# Sheet2.net
KiCad netlist of a schematic drawn in Altium Designer
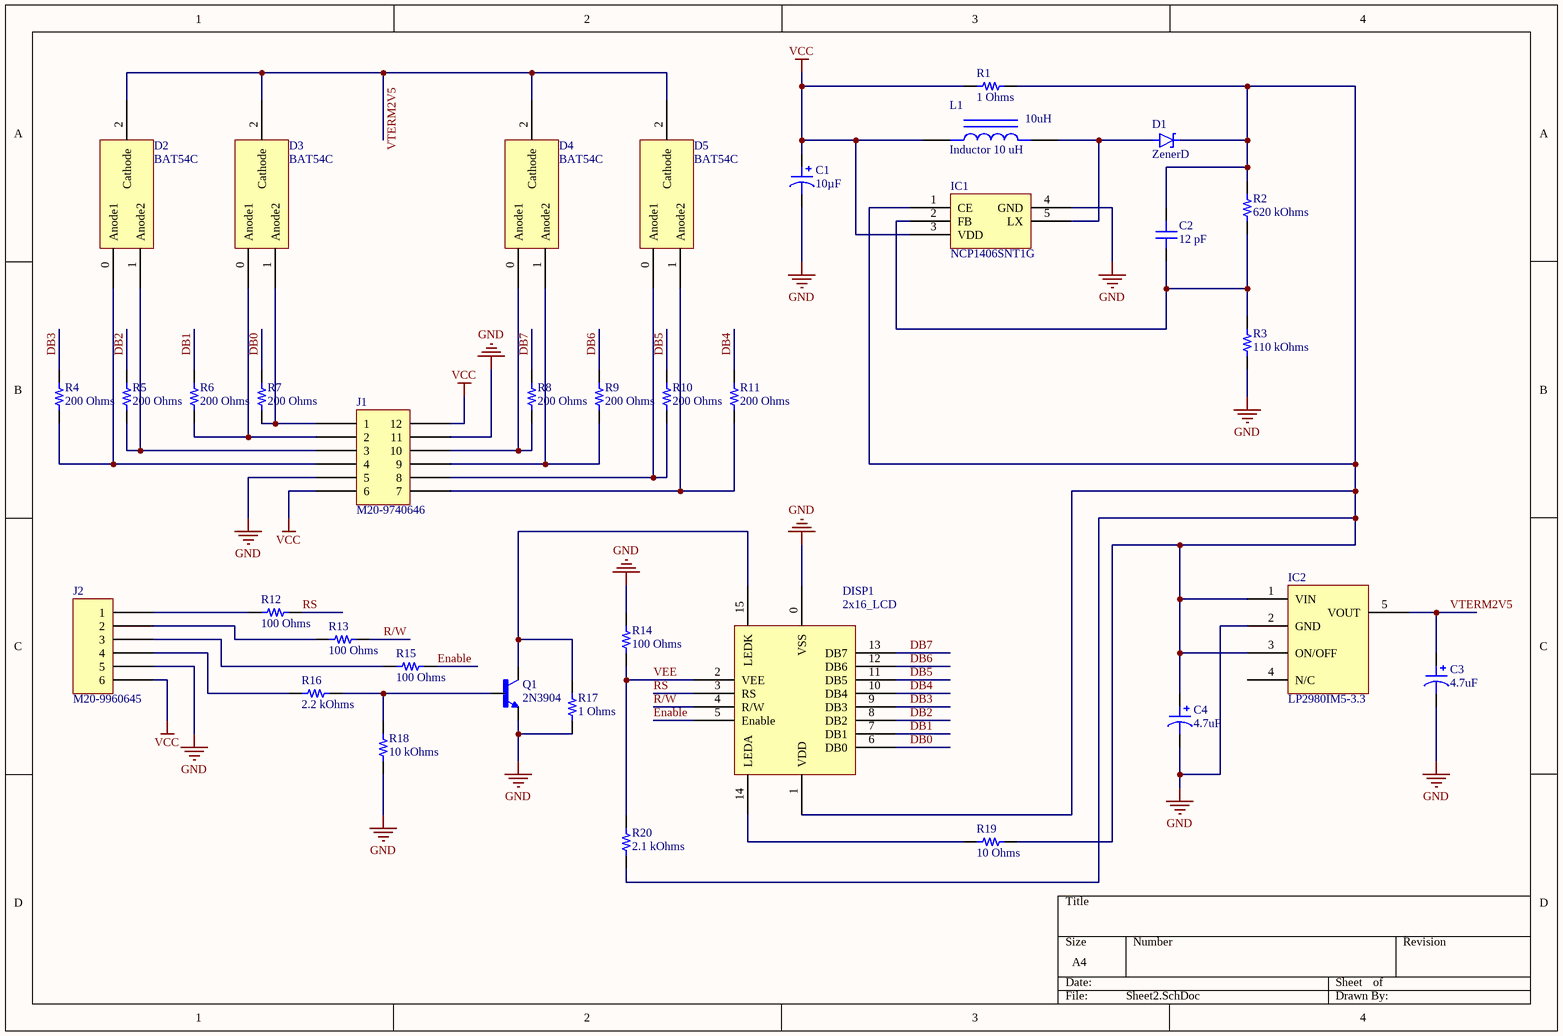
[diagram p0: Sheet2.SchDoc]

(export (version "E")
  (design (tool "Eeschema 10.0.6"))
  (components
    (comp (ref "C1")
      (value "10µF")
      (footprint "CAP TH ALUM ELEC D5.00mm S2.00mm H11.00mm")
      (description "CAP ALUM 10UF 20% 16V RADIAL")
      (fields
        (field (name "PART NUMBER") "ECE-A1CN100U")
        (field (name "MANUFACTURER") "Panasonic Electronic Components")
      )
      (libsource (lib "Celestial Altium Library - altium_library") (part "Polarised Capacitor"))
    )
    (comp (ref "C2")
      (value "12 pF")
      (footprint "CAP 0805_2012")
      (description "CAP CER 12PF 16V C0G/NP0 0805")
      (fields
        (field (name "PART NUMBER") "VJ0805A120FXJCW1BC")
        (field (name "MANUFACTURER") "Vishay Vitramon")
      )
      (libsource (lib "Celestial Altium Library - altium_library") (part "Capacitor"))
    )
    (comp (ref "C3")
      (value "4.7uF")
      (footprint "CAP TH ALUM ELEC D5.00mm S2.00mm H11.00mm")
      (description "CAP ALUM 4.7UF 20% 16V RADIAL")
      (fields
        (field (name "PART NUMBER") "ECE-A1CN100U")
        (field (name "MANUFACTURER") "Panasonic Electronic Components")
      )
      (libsource (lib "Celestial Altium Library - altium_library") (part "Polarised Capacitor"))
    )
    (comp (ref "C4")
      (value "4.7uF")
      (footprint "CAP TH ALUM ELEC D5.00mm S2.00mm H11.00mm")
      (description "CAP ALUM 4.7UF 20% 16V RADIAL")
      (fields
        (field (name "PART NUMBER") "ECE-A1CN100U")
        (field (name "MANUFACTURER") "Panasonic Electronic Components")
      )
      (libsource (lib "Celestial Altium Library - altium_library") (part "Polarised Capacitor"))
    )
    (comp (ref "D1") (value "ZenerD") (footprint "ZenerD") (libsource (lib "Schlib1") (part "ZenerD")))
    (comp (ref "D2") (value "BAT54C") (footprint "BAT54C") (libsource (lib "Schlib1") (part "BAT54C")))
    (comp (ref "D3") (value "BAT54C") (footprint "BAT54C") (libsource (lib "Schlib1") (part "BAT54C")))
    (comp (ref "D4") (value "BAT54C") (footprint "BAT54C") (libsource (lib "Schlib1") (part "BAT54C")))
    (comp (ref "D5") (value "BAT54C") (footprint "BAT54C") (libsource (lib "Schlib1") (part "BAT54C")))
    (comp (ref "DISP1")
      (value "2x16_LCD")
      (footprint "2x16_LCD")
      (libsource (lib "Schlib1") (part "2x16_LCD"))
    )
    (comp (ref "IC1")
      (value "NCP1406SNT1G")
      (footprint "NCP1406SNT1G")
      (libsource (lib "Schlib1") (part "NCP1406SNT1G"))
    )
    (comp (ref "IC2")
      (value "LP2980IM5-3.3")
      (footprint "LP2980IM5-3.3")
      (libsource (lib "Schlib1") (part "LP2980IM5-3.3"))
    )
    (comp (ref "J1")
      (value "M20-9740646")
      (footprint "HARWIN M20-9740645")
      (description "CONN HEADER R/A 12POS 2.54MM")
      (fields (field (name "MANUFACTURER") "Harwin Inc."))
      (libsource (lib "Celestial Altium Library - altium_library") (part "2X6 PIN DU"))
    )
    (comp (ref "J2")
      (value "M20-9960645")
      (footprint "HARWIN M20-9960645")
      (description "CONN HEADER R/A 6POS 2.54MM")
      (fields (field (name "MANUFACTURER") "Harwin Inc."))
      (libsource (lib "Celestial Altium Library - altium_library") (part "6 Pin"))
    )
    (comp (ref "L1")
      (value "Inductor 10 uH")
      (footprint "Inductor")
      (libsource (lib "Schlib1") (part "Inductor 2.2 uH"))
    )
    (comp (ref "Q1") (value "2N3904") (footprint "2N3904") (libsource (lib "Schlib1") (part "2N3904")))
    (comp (ref "R1")
      (value "1 Ohms")
      (footprint "RES 0805_2012")
      (description "RES 1 OHM 5% 1/4W 0805")
      (fields
        (field (name "PART NUMBER") "SG73S2ATTD1R0J")
        (field (name "MANUFACTURER") "KOA Speer Electronics, Inc.")
      )
      (libsource (lib "Celestial Altium Library - altium_library") (part "Resistor"))
    )
    (comp (ref "R2")
      (value "620 kOhms")
      (footprint "RES 0805_2012")
      (description "RES SMD 620K OHM 0.1% 1/4W 0805")
      (fields
        (field (name "PART NUMBER") "ERJ-PB6B6203V")
        (field (name "MANUFACTURER") "Panasonic Electronic Components")
      )
      (libsource (lib "Celestial Altium Library - altium_library") (part "Resistor"))
    )
    (comp (ref "R3")
      (value "110 kOhms")
      (footprint "RES 0805_2012")
      (description "RES 110K OHM 5% 1/4W 0805")
      (fields
        (field (name "PART NUMBER") "RK73B2ATTD114J")
        (field (name "MANUFACTURER") "KOA Speer Electronics, Inc.")
      )
      (libsource (lib "Celestial Altium Library - altium_library") (part "Resistor"))
    )
    (comp (ref "R4")
      (value "200 Ohms")
      (footprint "RES 0805_2012")
      (description "RES 200 OHM 5% 1/4W 0805")
      (fields
        (field (name "PART NUMBER") "RK73B2ATTD201J")
        (field (name "MANUFACTURER") "KOA Speer Electronics, Inc.")
      )
      (libsource (lib "Celestial Altium Library - altium_library") (part "Resistor"))
    )
    (comp (ref "R5")
      (value "200 Ohms")
      (footprint "RES 0805_2012")
      (description "RES 200 OHM 5% 1/4W 0805")
      (fields
        (field (name "PART NUMBER") "RK73B2ATTD201J")
        (field (name "MANUFACTURER") "KOA Speer Electronics, Inc.")
      )
      (libsource (lib "Celestial Altium Library - altium_library") (part "Resistor"))
    )
    (comp (ref "R6")
      (value "200 Ohms")
      (footprint "RES 0805_2012")
      (description "RES 200 OHM 5% 1/4W 0805")
      (fields
        (field (name "PART NUMBER") "RK73B2ATTD201J")
        (field (name "MANUFACTURER") "KOA Speer Electronics, Inc.")
      )
      (libsource (lib "Celestial Altium Library - altium_library") (part "Resistor"))
    )
    (comp (ref "R7")
      (value "200 Ohms")
      (footprint "RES 0805_2012")
      (description "RES 200 OHM 5% 1/4W 0805")
      (fields
        (field (name "PART NUMBER") "RK73B2ATTD201J")
        (field (name "MANUFACTURER") "KOA Speer Electronics, Inc.")
      )
      (libsource (lib "Celestial Altium Library - altium_library") (part "Resistor"))
    )
    (comp (ref "R8")
      (value "200 Ohms")
      (footprint "RES 0805_2012")
      (description "RES 200 OHM 5% 1/4W 0805")
      (fields
        (field (name "PART NUMBER") "RK73B2ATTD201J")
        (field (name "MANUFACTURER") "KOA Speer Electronics, Inc.")
      )
      (libsource (lib "Celestial Altium Library - altium_library") (part "Resistor"))
    )
    (comp (ref "R9")
      (value "200 Ohms")
      (footprint "RES 0805_2012")
      (description "RES 200 OHM 5% 1/4W 0805")
      (fields
        (field (name "PART NUMBER") "RK73B2ATTD201J")
        (field (name "MANUFACTURER") "KOA Speer Electronics, Inc.")
      )
      (libsource (lib "Celestial Altium Library - altium_library") (part "Resistor"))
    )
    (comp (ref "R10")
      (value "200 Ohms")
      (footprint "RES 0805_2012")
      (description "RES 200 OHM 5% 1/4W 0805")
      (fields
        (field (name "PART NUMBER") "RK73B2ATTD201J")
        (field (name "MANUFACTURER") "KOA Speer Electronics, Inc.")
      )
      (libsource (lib "Celestial Altium Library - altium_library") (part "Resistor"))
    )
    (comp (ref "R11")
      (value "200 Ohms")
      (footprint "RES 0805_2012")
      (description "RES 200 OHM 5% 1/4W 0805")
      (fields
        (field (name "PART NUMBER") "RK73B2ATTD201J")
        (field (name "MANUFACTURER") "KOA Speer Electronics, Inc.")
      )
      (libsource (lib "Celestial Altium Library - altium_library") (part "Resistor"))
    )
    (comp (ref "R12")
      (value "100 Ohms")
      (footprint "RES 0805_2012")
      (description "RES 100 OHM 5% 1/4W 0805")
      (fields
        (field (name "PART NUMBER") "RK73B2ATTD101J")
        (field (name "MANUFACTURER") "KOA Speer Electronics, Inc.")
      )
      (libsource (lib "Celestial Altium Library - altium_library") (part "Resistor"))
    )
    (comp (ref "R13")
      (value "100 Ohms")
      (footprint "RES 0805_2012")
      (description "RES 100 OHM 5% 1/4W 0805")
      (fields
        (field (name "PART NUMBER") "RK73B2ATTD101J")
        (field (name "MANUFACTURER") "KOA Speer Electronics, Inc.")
      )
      (libsource (lib "Celestial Altium Library - altium_library") (part "Resistor"))
    )
    (comp (ref "R14")
      (value "100 Ohms")
      (footprint "RES 0805_2012")
      (description "RES 100 OHM 5% 1/4W 0805")
      (fields
        (field (name "PART NUMBER") "RK73B2ATTD101J")
        (field (name "MANUFACTURER") "KOA Speer Electronics, Inc.")
      )
      (libsource (lib "Celestial Altium Library - altium_library") (part "Resistor"))
    )
    (comp (ref "R15")
      (value "100 Ohms")
      (footprint "RES 0805_2012")
      (description "RES 100 OHM 5% 1/4W 0805")
      (fields
        (field (name "PART NUMBER") "RK73B2ATTD101J")
        (field (name "MANUFACTURER") "KOA Speer Electronics, Inc.")
      )
      (libsource (lib "Celestial Altium Library - altium_library") (part "Resistor"))
    )
    (comp (ref "R16")
      (value "2.2 kOhms")
      (footprint "RES 0805_2012")
      (description "RES 2.2K OHM 5% 1/4W 0805")
      (fields
        (field (name "PART NUMBER") "RK73B2ATTD222J")
        (field (name "MANUFACTURER") "KOA Speer Electronics, Inc.")
      )
      (libsource (lib "Celestial Altium Library - altium_library") (part "Resistor"))
    )
    (comp (ref "R17")
      (value "1 Ohms")
      (footprint "RES 0805_2012")
      (description "RES 1 OHM 5% 1/4W 0805")
      (fields
        (field (name "PART NUMBER") "SG73S2ATTD1R0J")
        (field (name "MANUFACTURER") "KOA Speer Electronics, Inc.")
      )
      (libsource (lib "Celestial Altium Library - altium_library") (part "Resistor"))
    )
    (comp (ref "R18")
      (value "10 kOhms")
      (footprint "RES 0805_2012")
      (description "RES 10K OHM 1% 1/4W 0805")
      (fields
        (field (name "PART NUMBER") "SG73S2ATTD1002F")
        (field (name "MANUFACTURER") "KOA Speer Electronics, Inc.")
      )
      (libsource (lib "Celestial Altium Library - altium_library") (part "Resistor"))
    )
    (comp (ref "R19")
      (value "10 Ohms")
      (footprint "RES 0805_2012")
      (description "RES 10 OHM 1% 1/4W 0805")
      (fields
        (field (name "PART NUMBER") "RNCP0805FTD10R0")
        (field (name "MANUFACTURER") "Stackpole Electronics Inc")
      )
      (libsource (lib "Celestial Altium Library - altium_library") (part "Resistor"))
    )
    (comp (ref "R20")
      (value "2.1 kOhms")
      (footprint "RES 0805_2012")
      (description "RES 2.1K OHM 1% 1/4W 0805")
      (fields
        (field (name "PART NUMBER") "RK73H2ATTD2101F")
        (field (name "MANUFACTURER") "KOA Speer Electronics, Inc.")
      )
      (libsource (lib "Celestial Altium Library - altium_library") (part "Resistor"))
    )
  )
  (nets
    (net (code "2") (name "/DB0") (class "Default")
      (node (ref "DISP1") (pin "6") (pinfunction "DB0_6") (pintype "passive"))
      (node (ref "R7") (pin "1") (pinfunction "1_1") (pintype "passive"))
    )
    (net (code "3") (name "/DB1") (class "Default")
      (node (ref "DISP1") (pin "7") (pinfunction "DB1_7") (pintype "passive"))
      (node (ref "R6") (pin "2") (pinfunction "2_2") (pintype "passive"))
    )
    (net (code "4") (name "/DB2") (class "Default")
      (node (ref "DISP1") (pin "8") (pinfunction "DB2_8") (pintype "passive"))
      (node (ref "R5") (pin "1") (pinfunction "1_1") (pintype "passive"))
    )
    (net (code "5") (name "/DB3") (class "Default")
      (node (ref "DISP1") (pin "9") (pinfunction "DB3_9") (pintype "passive"))
      (node (ref "R4") (pin "1") (pinfunction "1_1") (pintype "passive"))
    )
    (net (code "6") (name "/DB4") (class "Default")
      (node (ref "DISP1") (pin "10") (pinfunction "DB4_10") (pintype "passive"))
      (node (ref "R11") (pin "1") (pinfunction "1_1") (pintype "passive"))
    )
    (net (code "7") (name "/DB5") (class "Default")
      (node (ref "DISP1") (pin "11") (pinfunction "DB5_11") (pintype "passive"))
      (node (ref "R10") (pin "1") (pinfunction "1_1") (pintype "passive"))
    )
    (net (code "8") (name "/DB6") (class "Default")
      (node (ref "DISP1") (pin "12") (pinfunction "DB6_12") (pintype "passive"))
      (node (ref "R9") (pin "1") (pinfunction "1_1") (pintype "passive"))
    )
    (net (code "9") (name "/DB7") (class "Default")
      (node (ref "DISP1") (pin "13") (pinfunction "DB7_13") (pintype "passive"))
      (node (ref "R8") (pin "1") (pinfunction "1_1") (pintype "passive"))
    )
    (net (code "10") (name "/Enable") (class "Default")
      (node (ref "DISP1") (pin "5") (pinfunction "Enable_5") (pintype "passive"))
      (node (ref "R15") (pin "2") (pinfunction "2_2") (pintype "passive"))
    )
    (net (code "11") (name "/RS") (class "Default")
      (node (ref "DISP1") (pin "3") (pinfunction "RS_3") (pintype "passive"))
      (node (ref "R12") (pin "2") (pinfunction "2_2") (pintype "passive"))
    )
    (net (code "12") (name "/R{slash}W") (class "Default")
      (node (ref "DISP1") (pin "4") (pinfunction "R/W_4") (pintype "passive"))
      (node (ref "R13") (pin "2") (pinfunction "2_2") (pintype "passive"))
    )
    (net (code "13") (name "/VEE") (class "Default")
      (node (ref "DISP1") (pin "2") (pinfunction "VEE_2") (pintype "passive"))
      (node (ref "R14") (pin "2") (pinfunction "2_2") (pintype "passive"))
      (node (ref "R20") (pin "2") (pinfunction "2_2") (pintype "passive"))
    )
    (net (code "14") (name "/VTERM2V5") (class "Default")
      (node (ref "C3") (pin "1") (pinfunction "1_1") (pintype "passive"))
      (node (ref "D2") (pin "2") (pinfunction "Cathode_2") (pintype "passive"))
      (node (ref "D3") (pin "2") (pinfunction "Cathode_2") (pintype "passive"))
      (node (ref "D4") (pin "2") (pinfunction "Cathode_2") (pintype "passive"))
      (node (ref "D5") (pin "2") (pinfunction "Cathode_2") (pintype "passive"))
      (node (ref "IC2") (pin "5") (pinfunction "VOUT_5") (pintype "passive"))
    )
    (net (code "15") (name "GND") (class "Default")
      (node (ref "C1") (pin "2") (pinfunction "2_2") (pintype "passive"))
      (node (ref "C3") (pin "2") (pinfunction "2_2") (pintype "passive"))
      (node (ref "C4") (pin "2") (pinfunction "2_2") (pintype "passive"))
      (node (ref "DISP1") (pin "0") (pinfunction "VSS_0") (pintype "passive"))
      (node (ref "IC1") (pin "4") (pinfunction "GND_4") (pintype "passive"))
      (node (ref "IC2") (pin "2") (pinfunction "GND_2") (pintype "passive"))
      (node (ref "J1") (pin "11") (pinfunction "11_11") (pintype "passive"))
      (node (ref "J1") (pin "5") (pinfunction "5_5") (pintype "passive"))
      (node (ref "J2") (pin "5") (pinfunction "5_5") (pintype "passive"))
      (node (ref "Q1") (pin "1") (pinfunction "E_1") (pintype "passive"))
      (node (ref "R14") (pin "1") (pinfunction "1_1") (pintype "passive"))
      (node (ref "R17") (pin "1") (pinfunction "1_1") (pintype "passive"))
      (node (ref "R18") (pin "1") (pinfunction "1_1") (pintype "passive"))
      (node (ref "R3") (pin "1") (pinfunction "1_1") (pintype "passive"))
    )
    (net (code "16") (name "Net-(D2-Anode1)") (class "Default")
      (node (ref "D2") (pin "0") (pinfunction "Anode1_0") (pintype "passive"))
      (node (ref "J1") (pin "4") (pinfunction "4_4") (pintype "passive"))
      (node (ref "R4") (pin "2") (pinfunction "2_2") (pintype "passive"))
    )
    (net (code "17") (name "Net-(D2-Anode2)") (class "Default")
      (node (ref "D2") (pin "1") (pinfunction "Anode2_1") (pintype "passive"))
      (node (ref "J1") (pin "3") (pinfunction "3_3") (pintype "passive"))
      (node (ref "R5") (pin "2") (pinfunction "2_2") (pintype "passive"))
    )
    (net (code "18") (name "Net-(D3-Anode1)") (class "Default")
      (node (ref "D3") (pin "0") (pinfunction "Anode1_0") (pintype "passive"))
      (node (ref "J1") (pin "2") (pinfunction "2_2") (pintype "passive"))
      (node (ref "R6") (pin "1") (pinfunction "1_1") (pintype "passive"))
    )
    (net (code "19") (name "Net-(D3-Anode2)") (class "Default")
      (node (ref "D3") (pin "1") (pinfunction "Anode2_1") (pintype "passive"))
      (node (ref "J1") (pin "1") (pinfunction "1_1") (pintype "passive"))
      (node (ref "R7") (pin "2") (pinfunction "2_2") (pintype "passive"))
    )
    (net (code "20") (name "Net-(D4-Anode1)") (class "Default")
      (node (ref "D4") (pin "0") (pinfunction "Anode1_0") (pintype "passive"))
      (node (ref "J1") (pin "10") (pinfunction "10_10") (pintype "passive"))
      (node (ref "R8") (pin "2") (pinfunction "2_2") (pintype "passive"))
    )
    (net (code "21") (name "Net-(D4-Anode2)") (class "Default")
      (node (ref "D4") (pin "1") (pinfunction "Anode2_1") (pintype "passive"))
      (node (ref "J1") (pin "9") (pinfunction "9_9") (pintype "passive"))
      (node (ref "R9") (pin "2") (pinfunction "2_2") (pintype "passive"))
    )
    (net (code "22") (name "Net-(D5-Anode1)") (class "Default")
      (node (ref "D5") (pin "0") (pinfunction "Anode1_0") (pintype "passive"))
      (node (ref "J1") (pin "8") (pinfunction "8_8") (pintype "passive"))
      (node (ref "R10") (pin "2") (pinfunction "2_2") (pintype "passive"))
    )
    (net (code "23") (name "Net-(D5-Anode2)") (class "Default")
      (node (ref "D5") (pin "1") (pinfunction "Anode2_1") (pintype "passive"))
      (node (ref "J1") (pin "7") (pinfunction "7_7") (pintype "passive"))
      (node (ref "R11") (pin "2") (pinfunction "2_2") (pintype "passive"))
    )
    (net (code "24") (name "Net-(DISP1-LEDA)") (class "Default")
      (node (ref "DISP1") (pin "14") (pinfunction "LEDA_14") (pintype "passive"))
      (node (ref "R19") (pin "1") (pinfunction "1_1") (pintype "passive"))
    )
    (net (code "25") (name "Net-(DISP1-LEDK)") (class "Default")
      (node (ref "DISP1") (pin "15") (pinfunction "LEDK_15") (pintype "passive"))
      (node (ref "Q1") (pin "3") (pinfunction "C_3") (pintype "passive"))
      (node (ref "R17") (pin "2") (pinfunction "2_2") (pintype "passive"))
    )
    (net (code "26") (name "Net-(DISP1-VDD)") (class "Default")
      (node (ref "C2") (pin "2") (pinfunction "2_2") (pintype "passive"))
      (node (ref "C4") (pin "1") (pinfunction "1_1") (pintype "passive"))
      (node (ref "D1") (pin "C") (pinfunction "C_C") (pintype "passive"))
      (node (ref "DISP1") (pin "1") (pinfunction "VDD_1") (pintype "passive"))
      (node (ref "IC1") (pin "1") (pinfunction "CE_1") (pintype "passive"))
      (node (ref "IC2") (pin "1") (pinfunction "VIN_1") (pintype "passive"))
      (node (ref "IC2") (pin "3") (pinfunction "ON/OFF_3") (pintype "passive"))
      (node (ref "R1") (pin "1") (pinfunction "1_1") (pintype "passive"))
      (node (ref "R19") (pin "2") (pinfunction "2_2") (pintype "passive"))
      (node (ref "R2") (pin "2") (pinfunction "2_2") (pintype "passive"))
      (node (ref "R20") (pin "1") (pinfunction "1_1") (pintype "passive"))
    )
    (net (code "27") (name "Net-(IC1-FB)") (class "Default")
      (node (ref "C2") (pin "1") (pinfunction "1_1") (pintype "passive"))
      (node (ref "IC1") (pin "2") (pinfunction "FB_2") (pintype "passive"))
      (node (ref "R2") (pin "1") (pinfunction "1_1") (pintype "passive"))
      (node (ref "R3") (pin "2") (pinfunction "2_2") (pintype "passive"))
    )
    (net (code "28") (name "Net-(IC1-LX)") (class "Default")
      (node (ref "D1") (pin "A") (pinfunction "A_A") (pintype "passive"))
      (node (ref "IC1") (pin "5") (pinfunction "LX_5") (pintype "passive"))
      (node (ref "L1") (pin "1") (pinfunction "2_1") (pintype "passive"))
    )
    (net (code "29") (name "Net-(J2-Pad1)") (class "Default")
      (node (ref "J2") (pin "1") (pinfunction "1_1") (pintype "passive"))
      (node (ref "R12") (pin "1") (pinfunction "1_1") (pintype "passive"))
    )
    (net (code "30") (name "Net-(J2-Pad2)") (class "Default")
      (node (ref "J2") (pin "2") (pinfunction "2_2") (pintype "passive"))
      (node (ref "R13") (pin "1") (pinfunction "1_1") (pintype "passive"))
    )
    (net (code "31") (name "Net-(J2-Pad3)") (class "Default")
      (node (ref "J2") (pin "3") (pinfunction "3_3") (pintype "passive"))
      (node (ref "R15") (pin "1") (pinfunction "1_1") (pintype "passive"))
    )
    (net (code "32") (name "Net-(J2-Pad4)") (class "Default")
      (node (ref "J2") (pin "4") (pinfunction "4_4") (pintype "passive"))
      (node (ref "R16") (pin "1") (pinfunction "1_1") (pintype "passive"))
    )
    (net (code "33") (name "Net-(Q1-B)") (class "Default")
      (node (ref "Q1") (pin "2") (pinfunction "B_2") (pintype "passive"))
      (node (ref "R16") (pin "2") (pinfunction "2_2") (pintype "passive"))
      (node (ref "R18") (pin "2") (pinfunction "2_2") (pintype "passive"))
    )
    (net (code "34") (name "VCC") (class "Default")
      (node (ref "C1") (pin "1") (pinfunction "1_1") (pintype "passive"))
      (node (ref "IC1") (pin "3") (pinfunction "VDD_3") (pintype "passive"))
      (node (ref "J1") (pin "12") (pinfunction "12_12") (pintype "passive"))
      (node (ref "J1") (pin "6") (pinfunction "6_6") (pintype "passive"))
      (node (ref "J2") (pin "6") (pinfunction "6_6") (pintype "passive"))
      (node (ref "L1") (pin "0") (pinfunction "1_0") (pintype "passive"))
      (node (ref "R1") (pin "2") (pinfunction "2_2") (pintype "passive"))
    )
    (net (code "35") (name "unconnected-(IC2-N{slash}C-Pad4)") (class "Default")
      (node (ref "IC2") (pin "4") (pinfunction "N/C_4") (pintype "passive"))
    )
  )
)
